# CDTV-SCSI-SD.net
KiCad netlist of a schematic drawn in EAGLE
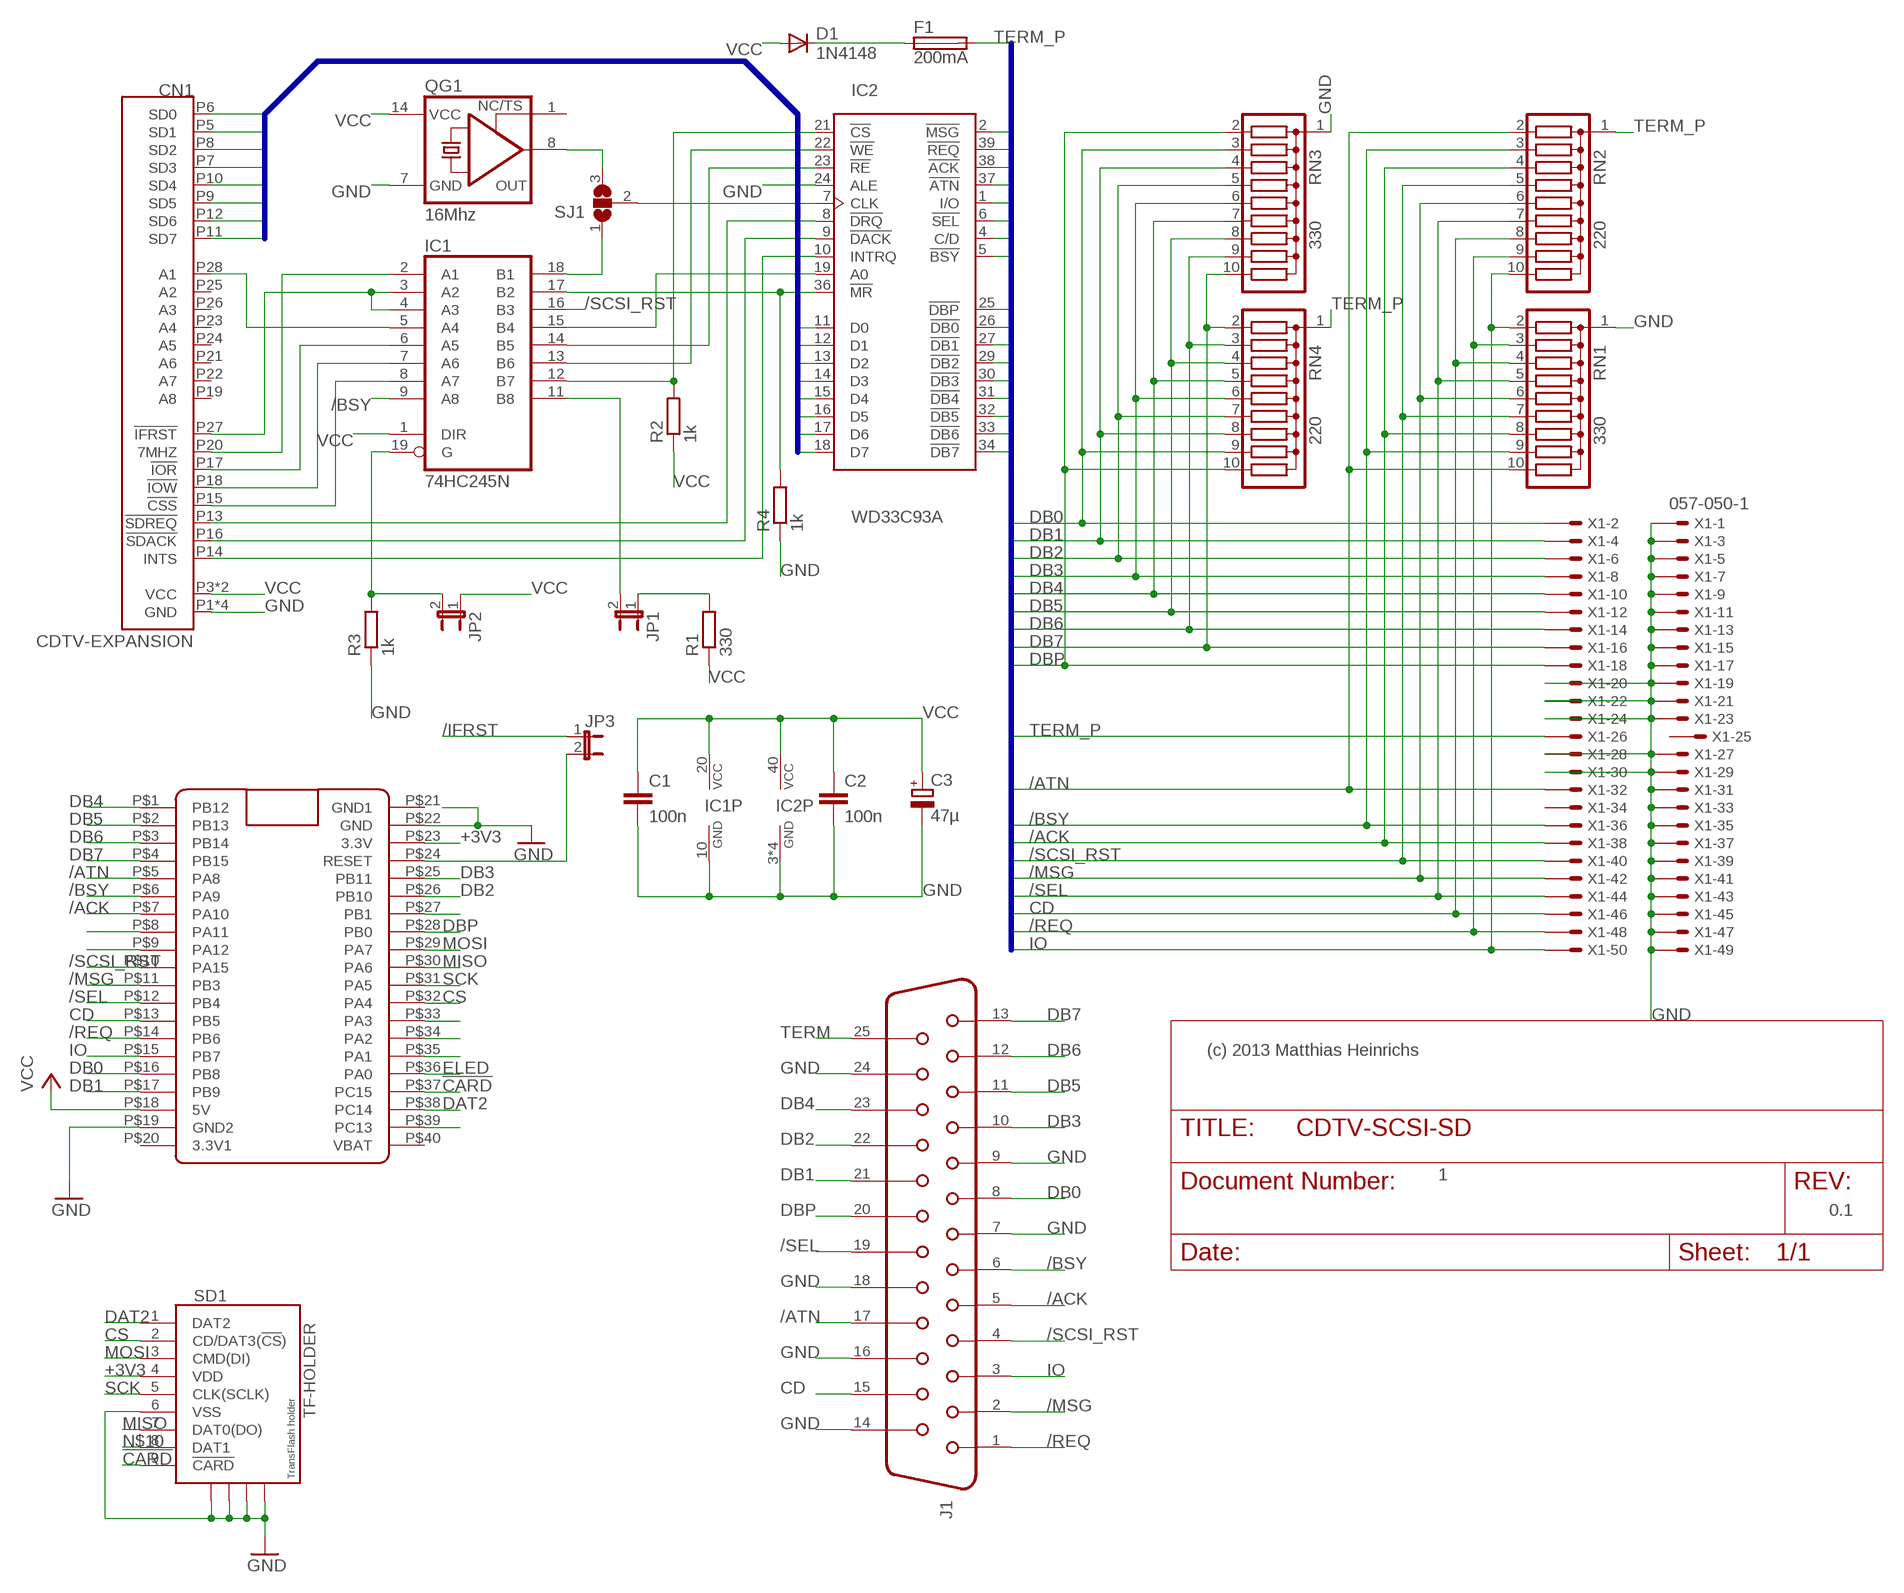
[diagram p0: schematic, sheet 1]

(export (version "E")
  (design (tool "Eeschema 10.0.6"))
  (components
    (comp (ref "C1")
      (value "100n")
      (footprint "eagle-import:C025-024X044")
      (libsource (lib "eagle-import") (part "C-EU025-024X044"))
    )
    (comp (ref "C2")
      (value "100n")
      (footprint "eagle-import:C025-024X044")
      (libsource (lib "eagle-import") (part "C-EU025-024X044"))
    )
    (comp (ref "C3")
      (value "47µ")
      (footprint "eagle-import:E2,5-6E")
      (libsource (lib "eagle-import") (part "CPOL-EUE2,5-6E"))
    )
    (comp (ref "CN1")
      (value "CDTV-EXPANSION")
      (footprint "eagle-import:CDTV-SLOT")
      (libsource (lib "eagle-import") (part "CDTV-EXPANSION"))
    )
    (comp (ref "D1")
      (value "1N4148")
      (footprint "eagle-import:DO35-7")
      (libsource (lib "eagle-import") (part "1N4148DO35-7"))
    )
    (comp (ref "F1")
      (value "200mA")
      (footprint "eagle-import:TE5")
      (libsource (lib "eagle-import") (part "FUSETE5"))
    )
    (comp (ref "IC1")
      (value "74HC245N")
      (footprint "eagle-import:DIL20")
      (libsource (lib "eagle-import") (part "74245NHC"))
    )
    (comp (ref "IC2")
      (value "WD33C93A")
      (footprint "eagle-import:DIP40-6")
      (libsource (lib "eagle-import") (part "WD33C93"))
    )
    (comp (ref "J1")
      (value "61802529321")
      (footprint "eagle-import:61802529321")
      (libsource (lib "eagle-import") (part "61802529321"))
    )
    (comp (ref "JP1")
      (value "JP1E")
      (footprint "eagle-import:JP1")
      (libsource (lib "eagle-import") (part "JP1E"))
    )
    (comp (ref "JP2")
      (value "JP1E")
      (footprint "eagle-import:JP1")
      (libsource (lib "eagle-import") (part "JP1E"))
    )
    (comp (ref "JP3")
      (value "JP1E")
      (footprint "eagle-import:JP1")
      (libsource (lib "eagle-import") (part "JP1E"))
    )
    (comp (ref "QG1")
      (value "16Mhz")
      (footprint "eagle-import:DIL14S")
      (libsource (lib "eagle-import") (part "XO-14"))
    )
    (comp (ref "R1")
      (value "330")
      (footprint "eagle-import:0207_7")
      (libsource (lib "eagle-import") (part "R-EU_0207/7"))
    )
    (comp (ref "R2")
      (value "1k")
      (footprint "eagle-import:0207_7")
      (libsource (lib "eagle-import") (part "R-EU_0207/7"))
    )
    (comp (ref "R3")
      (value "1k")
      (footprint "eagle-import:0207_7")
      (libsource (lib "eagle-import") (part "R-EU_0207/7"))
    )
    (comp (ref "R4")
      (value "1k")
      (footprint "eagle-import:0207_7")
      (libsource (lib "eagle-import") (part "R-EU_0207/7"))
    )
    (comp (ref "RN1")
      (value "330")
      (footprint "eagle-import:SIL10")
      (libsource (lib "eagle-import") (part "G09R"))
    )
    (comp (ref "RN2")
      (value "220")
      (footprint "eagle-import:SIL10")
      (libsource (lib "eagle-import") (part "G09R"))
    )
    (comp (ref "RN3")
      (value "330")
      (footprint "eagle-import:SIL10")
      (libsource (lib "eagle-import") (part "G09R"))
    )
    (comp (ref "RN4")
      (value "220")
      (footprint "eagle-import:SIL10")
      (libsource (lib "eagle-import") (part "G09R"))
    )
    (comp (ref "SD1")
      (value "TF-HOLDER")
      (footprint "eagle-import:TF-PULL")
      (libsource (lib "eagle-import") (part "TF-HOLDER"))
    )
    (comp (ref "SJ1")
      (value "SJ2W")
      (footprint "eagle-import:SJ_2")
      (libsource (lib "eagle-import") (part "SJ2W"))
    )
    (comp (ref "U$1")
      (value "BLUE_PILL")
      (footprint "eagle-import:BLUE_PILL")
      (libsource (lib "eagle-import") (part "BLUE_PILL"))
    )
    (comp (ref "X1")
      (value "057-050-1")
      (footprint "eagle-import:057-050-1")
      (libsource (lib "eagle-import") (part "057-050-1"))
    )
  )
  (nets
    (net (code "1") (name "/+3V3") (class "Default")
      (node (ref "SD1") (pin "4") (pinfunction "VDD_4") (pintype "power_in"))
      (node (ref "U$1") (pin "P$23") (pinfunction "3.3V_P$23") (pintype "bidirectional"))
    )
    (net (code "2") (name "/CD") (class "Default")
      (node (ref "IC2") (pin "4") (pinfunction "C/D_4") (pintype "bidirectional"))
      (node (ref "J1") (pin "15") (pinfunction "15_15") (pintype "bidirectional"))
      (node (ref "RN1") (pin "4") (pinfunction "4_4") (pintype "passive"))
      (node (ref "RN2") (pin "8") (pinfunction "8_8") (pintype "passive"))
      (node (ref "U$1") (pin "P$13") (pinfunction "PB5_P$13") (pintype "bidirectional"))
      (node (ref "X1") (pin "46") (pinfunction "S_46") (pintype "passive"))
    )
    (net (code "3") (name "/CS") (class "Default")
      (node (ref "SD1") (pin "2") (pinfunction "CD/DAT3(~{CS})_2") (pintype "bidirectional"))
      (node (ref "U$1") (pin "P$32") (pinfunction "PA4_P$32") (pintype "bidirectional"))
    )
    (net (code "4") (name "/DAT2") (class "Default")
      (node (ref "SD1") (pin "1") (pinfunction "DAT2_1") (pintype "bidirectional"))
      (node (ref "U$1") (pin "P$38") (pinfunction "PC14_P$38") (pintype "bidirectional"))
    )
    (net (code "5") (name "/DB0") (class "Default")
      (node (ref "IC2") (pin "26") (pinfunction "~{DB0}_26") (pintype "bidirectional"))
      (node (ref "J1") (pin "8") (pinfunction "8_8") (pintype "bidirectional"))
      (node (ref "RN3") (pin "3") (pinfunction "3_3") (pintype "passive"))
      (node (ref "RN4") (pin "9") (pinfunction "9_9") (pintype "passive"))
      (node (ref "U$1") (pin "P$16") (pinfunction "PB8_P$16") (pintype "bidirectional"))
      (node (ref "X1") (pin "2") (pinfunction "S_2") (pintype "passive"))
    )
    (net (code "6") (name "/DB1") (class "Default")
      (node (ref "IC2") (pin "27") (pinfunction "~{DB1}_27") (pintype "bidirectional"))
      (node (ref "J1") (pin "21") (pinfunction "21_21") (pintype "bidirectional"))
      (node (ref "RN3") (pin "4") (pinfunction "4_4") (pintype "passive"))
      (node (ref "RN4") (pin "8") (pinfunction "8_8") (pintype "passive"))
      (node (ref "U$1") (pin "P$17") (pinfunction "PB9_P$17") (pintype "bidirectional"))
      (node (ref "X1") (pin "4") (pinfunction "S_4") (pintype "passive"))
    )
    (net (code "7") (name "/DB2") (class "Default")
      (node (ref "IC2") (pin "29") (pinfunction "~{DB2}_29") (pintype "bidirectional"))
      (node (ref "J1") (pin "22") (pinfunction "22_22") (pintype "bidirectional"))
      (node (ref "RN3") (pin "5") (pinfunction "5_5") (pintype "passive"))
      (node (ref "RN4") (pin "7") (pinfunction "7_7") (pintype "passive"))
      (node (ref "U$1") (pin "P$26") (pinfunction "PB10_P$26") (pintype "bidirectional"))
      (node (ref "X1") (pin "6") (pinfunction "S_6") (pintype "passive"))
    )
    (net (code "8") (name "/DB3") (class "Default")
      (node (ref "IC2") (pin "30") (pinfunction "~{DB3}_30") (pintype "bidirectional"))
      (node (ref "J1") (pin "10") (pinfunction "10_10") (pintype "bidirectional"))
      (node (ref "RN3") (pin "6") (pinfunction "6_6") (pintype "passive"))
      (node (ref "RN4") (pin "6") (pinfunction "6_6") (pintype "passive"))
      (node (ref "U$1") (pin "P$25") (pinfunction "PB11_P$25") (pintype "bidirectional"))
      (node (ref "X1") (pin "8") (pinfunction "S_8") (pintype "passive"))
    )
    (net (code "9") (name "/DB4") (class "Default")
      (node (ref "IC2") (pin "31") (pinfunction "~{DB4}_31") (pintype "bidirectional"))
      (node (ref "J1") (pin "23") (pinfunction "23_23") (pintype "bidirectional"))
      (node (ref "RN3") (pin "7") (pinfunction "7_7") (pintype "passive"))
      (node (ref "RN4") (pin "5") (pinfunction "5_5") (pintype "passive"))
      (node (ref "U$1") (pin "P$1") (pinfunction "PB12_P$1") (pintype "bidirectional"))
      (node (ref "X1") (pin "10") (pinfunction "S_10") (pintype "passive"))
    )
    (net (code "10") (name "/DB5") (class "Default")
      (node (ref "IC2") (pin "32") (pinfunction "~{DB5}_32") (pintype "bidirectional"))
      (node (ref "J1") (pin "11") (pinfunction "11_11") (pintype "bidirectional"))
      (node (ref "RN3") (pin "8") (pinfunction "8_8") (pintype "passive"))
      (node (ref "RN4") (pin "4") (pinfunction "4_4") (pintype "passive"))
      (node (ref "U$1") (pin "P$2") (pinfunction "PB13_P$2") (pintype "bidirectional"))
      (node (ref "X1") (pin "12") (pinfunction "S_12") (pintype "passive"))
    )
    (net (code "11") (name "/DB6") (class "Default")
      (node (ref "IC2") (pin "33") (pinfunction "~{DB6}_33") (pintype "bidirectional"))
      (node (ref "J1") (pin "12") (pinfunction "12_12") (pintype "bidirectional"))
      (node (ref "RN3") (pin "9") (pinfunction "9_9") (pintype "passive"))
      (node (ref "RN4") (pin "3") (pinfunction "3_3") (pintype "passive"))
      (node (ref "U$1") (pin "P$3") (pinfunction "PB14_P$3") (pintype "bidirectional"))
      (node (ref "X1") (pin "14") (pinfunction "S_14") (pintype "passive"))
    )
    (net (code "12") (name "/DB7") (class "Default")
      (node (ref "IC2") (pin "34") (pinfunction "~{DB7}_34") (pintype "bidirectional"))
      (node (ref "J1") (pin "13") (pinfunction "13_13") (pintype "bidirectional"))
      (node (ref "RN3") (pin "10") (pinfunction "10_10") (pintype "passive"))
      (node (ref "RN4") (pin "2") (pinfunction "2_2") (pintype "passive"))
      (node (ref "U$1") (pin "P$4") (pinfunction "PB15_P$4") (pintype "bidirectional"))
      (node (ref "X1") (pin "16") (pinfunction "S_16") (pintype "passive"))
    )
    (net (code "13") (name "/DBP") (class "Default")
      (node (ref "IC2") (pin "25") (pinfunction "~{DBP}_25") (pintype "bidirectional"))
      (node (ref "J1") (pin "20") (pinfunction "20_20") (pintype "bidirectional"))
      (node (ref "RN3") (pin "2") (pinfunction "2_2") (pintype "passive"))
      (node (ref "RN4") (pin "10") (pinfunction "10_10") (pintype "passive"))
      (node (ref "U$1") (pin "P$28") (pinfunction "PB0_P$28") (pintype "bidirectional"))
      (node (ref "X1") (pin "18") (pinfunction "S_18") (pintype "passive"))
    )
    (net (code "14") (name "/ELED") (class "Default")
      (node (ref "U$1") (pin "P$36") (pinfunction "PA0_P$36") (pintype "bidirectional"))
    )
    (net (code "15") (name "/GND1") (class "Default")
      (node (ref "U$1") (pin "P$21") (pinfunction "GND1_P$21") (pintype "power_in"))
    )
    (net (code "16") (name "/IO") (class "Default")
      (node (ref "IC2") (pin "1") (pinfunction "I/O_1") (pintype "bidirectional"))
      (node (ref "J1") (pin "3") (pinfunction "3_3") (pintype "bidirectional"))
      (node (ref "RN1") (pin "2") (pinfunction "2_2") (pintype "passive"))
      (node (ref "RN2") (pin "10") (pinfunction "10_10") (pintype "passive"))
      (node (ref "U$1") (pin "P$15") (pinfunction "PB7_P$15") (pintype "bidirectional"))
      (node (ref "X1") (pin "50") (pinfunction "S_50") (pintype "passive"))
    )
    (net (code "17") (name "/MISO") (class "Default")
      (node (ref "SD1") (pin "7") (pinfunction "DAT0(DO)_7") (pintype "bidirectional"))
      (node (ref "U$1") (pin "P$30") (pinfunction "PA6_P$30") (pintype "bidirectional"))
    )
    (net (code "18") (name "/MOSI") (class "Default")
      (node (ref "SD1") (pin "3") (pinfunction "CMD(DI)_3") (pintype "bidirectional"))
      (node (ref "U$1") (pin "P$29") (pinfunction "PA7_P$29") (pintype "bidirectional"))
    )
    (net (code "19") (name "/N$10") (class "Default")
      (node (ref "SD1") (pin "8") (pinfunction "DAT1_8") (pintype "bidirectional"))
    )
    (net (code "20") (name "/SCK") (class "Default")
      (node (ref "SD1") (pin "5") (pinfunction "CLK(SCLK)_5") (pintype "input"))
      (node (ref "U$1") (pin "P$31") (pinfunction "PA5_P$31") (pintype "bidirectional"))
    )
    (net (code "21") (name "/SD0") (class "Default")
      (node (ref "CN1") (pin "P6") (pinfunction "SD0_P6") (pintype "bidirectional"))
      (node (ref "IC2") (pin "11") (pinfunction "D0_11") (pintype "bidirectional"))
    )
    (net (code "22") (name "/SD1") (class "Default")
      (node (ref "CN1") (pin "P5") (pinfunction "SD1_P5") (pintype "bidirectional"))
      (node (ref "IC2") (pin "12") (pinfunction "D1_12") (pintype "bidirectional"))
    )
    (net (code "23") (name "/SD2") (class "Default")
      (node (ref "CN1") (pin "P8") (pinfunction "SD2_P8") (pintype "bidirectional"))
      (node (ref "IC2") (pin "13") (pinfunction "D2_13") (pintype "bidirectional"))
    )
    (net (code "24") (name "/SD3") (class "Default")
      (node (ref "CN1") (pin "P7") (pinfunction "SD3_P7") (pintype "bidirectional"))
      (node (ref "IC2") (pin "14") (pinfunction "D3_14") (pintype "bidirectional"))
    )
    (net (code "25") (name "/SD4") (class "Default")
      (node (ref "CN1") (pin "P10") (pinfunction "SD4_P10") (pintype "bidirectional"))
      (node (ref "IC2") (pin "15") (pinfunction "D4_15") (pintype "bidirectional"))
    )
    (net (code "26") (name "/SD5") (class "Default")
      (node (ref "CN1") (pin "P9") (pinfunction "SD5_P9") (pintype "bidirectional"))
      (node (ref "IC2") (pin "16") (pinfunction "D5_16") (pintype "bidirectional"))
    )
    (net (code "27") (name "/SD6") (class "Default")
      (node (ref "CN1") (pin "P12") (pinfunction "SD6_P12") (pintype "bidirectional"))
      (node (ref "IC2") (pin "17") (pinfunction "D6_17") (pintype "bidirectional"))
    )
    (net (code "28") (name "/SD7") (class "Default")
      (node (ref "CN1") (pin "P11") (pinfunction "SD7_P11") (pintype "bidirectional"))
      (node (ref "IC2") (pin "18") (pinfunction "D7_18") (pintype "bidirectional"))
    )
    (net (code "29") (name "/TERM") (class "Default")
      (node (ref "J1") (pin "25") (pinfunction "25_25") (pintype "bidirectional"))
    )
    (net (code "30") (name "/TERM_P") (class "Default")
      (node (ref "F1") (pin "2") (pinfunction "2_2") (pintype "passive"))
      (node (ref "RN2") (pin "1") (pinfunction "1_1") (pintype "passive"))
      (node (ref "RN4") (pin "1") (pinfunction "1_1") (pintype "passive"))
      (node (ref "X1") (pin "26") (pinfunction "S_26") (pintype "passive"))
    )
    (net (code "31") (name "/{slash}ACK") (class "Default")
      (node (ref "IC2") (pin "38") (pinfunction "~{ACK}_38") (pintype "bidirectional"))
      (node (ref "J1") (pin "5") (pinfunction "5_5") (pintype "bidirectional"))
      (node (ref "RN1") (pin "8") (pinfunction "8_8") (pintype "passive"))
      (node (ref "RN2") (pin "4") (pinfunction "4_4") (pintype "passive"))
      (node (ref "U$1") (pin "P$7") (pinfunction "PA10_P$7") (pintype "bidirectional"))
      (node (ref "X1") (pin "38") (pinfunction "S_38") (pintype "passive"))
    )
    (net (code "32") (name "/{slash}ATN") (class "Default")
      (node (ref "IC2") (pin "37") (pinfunction "~{ATN}_37") (pintype "bidirectional"))
      (node (ref "J1") (pin "17") (pinfunction "17_17") (pintype "bidirectional"))
      (node (ref "RN1") (pin "10") (pinfunction "10_10") (pintype "passive"))
      (node (ref "RN2") (pin "2") (pinfunction "2_2") (pintype "passive"))
      (node (ref "U$1") (pin "P$5") (pinfunction "PA8_P$5") (pintype "bidirectional"))
      (node (ref "X1") (pin "32") (pinfunction "S_32") (pintype "passive"))
    )
    (net (code "33") (name "/{slash}BSY") (class "Default")
      (node (ref "IC1") (pin "9") (pinfunction "A8_9") (pintype "bidirectional"))
      (node (ref "IC2") (pin "5") (pinfunction "~{BSY}_5") (pintype "bidirectional"))
      (node (ref "J1") (pin "6") (pinfunction "6_6") (pintype "bidirectional"))
      (node (ref "RN1") (pin "9") (pinfunction "9_9") (pintype "passive"))
      (node (ref "RN2") (pin "3") (pinfunction "3_3") (pintype "passive"))
      (node (ref "U$1") (pin "P$6") (pinfunction "PA9_P$6") (pintype "bidirectional"))
      (node (ref "X1") (pin "36") (pinfunction "S_36") (pintype "passive"))
    )
    (net (code "34") (name "/{slash}IFRST") (class "Default")
      (node (ref "CN1") (pin "P27") (pinfunction "~{IFRST}_P27") (pintype "output"))
      (node (ref "IC1") (pin "3") (pinfunction "A2_3") (pintype "bidirectional"))
      (node (ref "IC1") (pin "4") (pinfunction "A3_4") (pintype "bidirectional"))
      (node (ref "JP3") (pin "1") (pinfunction "1_1") (pintype "passive"))
    )
    (net (code "35") (name "/{slash}MSG") (class "Default")
      (node (ref "IC2") (pin "2") (pinfunction "~{MSG}_2") (pintype "bidirectional"))
      (node (ref "J1") (pin "2") (pinfunction "2_2") (pintype "bidirectional"))
      (node (ref "RN1") (pin "6") (pinfunction "6_6") (pintype "passive"))
      (node (ref "RN2") (pin "6") (pinfunction "6_6") (pintype "passive"))
      (node (ref "U$1") (pin "P$11") (pinfunction "PB3_P$11") (pintype "bidirectional"))
      (node (ref "X1") (pin "42") (pinfunction "S_42") (pintype "passive"))
    )
    (net (code "36") (name "/{slash}REQ") (class "Default")
      (node (ref "IC2") (pin "39") (pinfunction "~{REQ}_39") (pintype "bidirectional"))
      (node (ref "J1") (pin "1") (pinfunction "1_1") (pintype "bidirectional"))
      (node (ref "RN1") (pin "3") (pinfunction "3_3") (pintype "passive"))
      (node (ref "RN2") (pin "9") (pinfunction "9_9") (pintype "passive"))
      (node (ref "U$1") (pin "P$14") (pinfunction "PB6_P$14") (pintype "bidirectional"))
      (node (ref "X1") (pin "48") (pinfunction "S_48") (pintype "passive"))
    )
    (net (code "37") (name "/{slash}SCSI_RST") (class "Default")
      (node (ref "IC1") (pin "16") (pinfunction "B3_16") (pintype "bidirectional"))
      (node (ref "J1") (pin "4") (pinfunction "4_4") (pintype "bidirectional"))
      (node (ref "RN1") (pin "7") (pinfunction "7_7") (pintype "passive"))
      (node (ref "RN2") (pin "5") (pinfunction "5_5") (pintype "passive"))
      (node (ref "U$1") (pin "P$10") (pinfunction "PA15_P$10") (pintype "bidirectional"))
      (node (ref "X1") (pin "40") (pinfunction "S_40") (pintype "passive"))
    )
    (net (code "38") (name "/{slash}SEL") (class "Default")
      (node (ref "IC2") (pin "6") (pinfunction "~{SEL}_6") (pintype "bidirectional"))
      (node (ref "J1") (pin "19") (pinfunction "19_19") (pintype "bidirectional"))
      (node (ref "RN1") (pin "5") (pinfunction "5_5") (pintype "passive"))
      (node (ref "RN2") (pin "7") (pinfunction "7_7") (pintype "passive"))
      (node (ref "U$1") (pin "P$12") (pinfunction "PB4_P$12") (pintype "bidirectional"))
      (node (ref "X1") (pin "44") (pinfunction "S_44") (pintype "passive"))
    )
    (net (code "39") (name "/~{CARD}") (class "Default")
      (node (ref "SD1") (pin "9") (pinfunction "~{CARD}_9") (pintype "passive"))
      (node (ref "U$1") (pin "P$37") (pinfunction "PC15_P$37") (pintype "bidirectional"))
    )
    (net (code "40") (name "GND") (class "Default")
      (node (ref "C1") (pin "2") (pinfunction "2_2") (pintype "passive"))
      (node (ref "C2") (pin "2") (pinfunction "2_2") (pintype "passive"))
      (node (ref "C3") (pin "-") (pinfunction "-_-") (pintype "passive"))
      (node (ref "CN1") (pin "P1") (pinfunction "GND_P1") (pintype "power_in"))
      (node (ref "CN1") (pin "P2") (pinfunction "GND_P2") (pintype "power_in"))
      (node (ref "CN1") (pin "P29") (pinfunction "GND_P29") (pintype "power_in"))
      (node (ref "CN1") (pin "P30") (pinfunction "GND_P30") (pintype "power_in"))
      (node (ref "IC1") (pin "10") (pinfunction "GND_10") (pintype "power_in"))
      (node (ref "IC2") (pin "20") (pinfunction "GND1_20") (pintype "power_in"))
      (node (ref "IC2") (pin "24") (pinfunction "ALE_24") (pintype "bidirectional"))
      (node (ref "IC2") (pin "28") (pinfunction "GND1_28") (pintype "power_in"))
      (node (ref "IC2") (pin "3") (pinfunction "GND1_3") (pintype "power_in"))
      (node (ref "IC2") (pin "35") (pinfunction "GND1_35") (pintype "power_in"))
      (node (ref "J1") (pin "14") (pinfunction "14_14") (pintype "bidirectional"))
      (node (ref "J1") (pin "16") (pinfunction "16_16") (pintype "bidirectional"))
      (node (ref "J1") (pin "18") (pinfunction "18_18") (pintype "bidirectional"))
      (node (ref "J1") (pin "24") (pinfunction "24_24") (pintype "bidirectional"))
      (node (ref "J1") (pin "7") (pinfunction "7_7") (pintype "bidirectional"))
      (node (ref "J1") (pin "9") (pinfunction "9_9") (pintype "bidirectional"))
      (node (ref "QG1") (pin "7") (pinfunction "GND_7") (pintype "power_in"))
      (node (ref "R3") (pin "1") (pinfunction "1_1") (pintype "passive"))
      (node (ref "R4") (pin "1") (pinfunction "1_1") (pintype "passive"))
      (node (ref "RN1") (pin "1") (pinfunction "1_1") (pintype "passive"))
      (node (ref "RN3") (pin "1") (pinfunction "1_1") (pintype "passive"))
      (node (ref "SD1") (pin "6") (pinfunction "VSS_6") (pintype "power_in"))
      (node (ref "SD1") (pin "S1") (pinfunction "S1_S1") (pintype "passive"))
      (node (ref "SD1") (pin "S2") (pinfunction "S2_S2") (pintype "passive"))
      (node (ref "SD1") (pin "S3") (pinfunction "S3_S3") (pintype "passive"))
      (node (ref "SD1") (pin "S4") (pinfunction "S4_S4") (pintype "passive"))
      (node (ref "U$1") (pin "P$19") (pinfunction "GND2_P$19") (pintype "bidirectional"))
      (node (ref "U$1") (pin "P$22") (pinfunction "GND_P$22") (pintype "bidirectional"))
      (node (ref "X1") (pin "1") (pinfunction "S_1") (pintype "passive"))
      (node (ref "X1") (pin "11") (pinfunction "S_11") (pintype "passive"))
      (node (ref "X1") (pin "13") (pinfunction "S_13") (pintype "passive"))
      (node (ref "X1") (pin "15") (pinfunction "S_15") (pintype "passive"))
      (node (ref "X1") (pin "17") (pinfunction "S_17") (pintype "passive"))
      (node (ref "X1") (pin "19") (pinfunction "S_19") (pintype "passive"))
      (node (ref "X1") (pin "20") (pinfunction "S_20") (pintype "passive"))
      (node (ref "X1") (pin "21") (pinfunction "S_21") (pintype "passive"))
      (node (ref "X1") (pin "22") (pinfunction "S_22") (pintype "passive"))
      (node (ref "X1") (pin "23") (pinfunction "S_23") (pintype "passive"))
      (node (ref "X1") (pin "24") (pinfunction "S_24") (pintype "passive"))
      (node (ref "X1") (pin "27") (pinfunction "S_27") (pintype "passive"))
      (node (ref "X1") (pin "28") (pinfunction "S_28") (pintype "passive"))
      (node (ref "X1") (pin "29") (pinfunction "S_29") (pintype "passive"))
      (node (ref "X1") (pin "3") (pinfunction "S_3") (pintype "passive"))
      (node (ref "X1") (pin "30") (pinfunction "S_30") (pintype "passive"))
      (node (ref "X1") (pin "31") (pinfunction "S_31") (pintype "passive"))
      (node (ref "X1") (pin "33") (pinfunction "S_33") (pintype "passive"))
      (node (ref "X1") (pin "35") (pinfunction "S_35") (pintype "passive"))
      (node (ref "X1") (pin "37") (pinfunction "S_37") (pintype "passive"))
      (node (ref "X1") (pin "39") (pinfunction "S_39") (pintype "passive"))
      (node (ref "X1") (pin "41") (pinfunction "S_41") (pintype "passive"))
      (node (ref "X1") (pin "43") (pinfunction "S_43") (pintype "passive"))
      (node (ref "X1") (pin "45") (pinfunction "S_45") (pintype "passive"))
      (node (ref "X1") (pin "47") (pinfunction "S_47") (pintype "passive"))
      (node (ref "X1") (pin "49") (pinfunction "S_49") (pintype "passive"))
      (node (ref "X1") (pin "5") (pinfunction "S_5") (pintype "passive"))
      (node (ref "X1") (pin "7") (pinfunction "S_7") (pintype "passive"))
      (node (ref "X1") (pin "9") (pinfunction "S_9") (pintype "passive"))
    )
    (net (code "41") (name "Net-(CN1-7MHZ)") (class "Default")
      (node (ref "CN1") (pin "P20") (pinfunction "7MHZ_P20") (pintype "output"))
      (node (ref "IC1") (pin "2") (pinfunction "A1_2") (pintype "bidirectional"))
    )
    (net (code "42") (name "Net-(CN1-A1)") (class "Default")
      (node (ref "CN1") (pin "P28") (pinfunction "A1_P28") (pintype "output"))
      (node (ref "IC1") (pin "5") (pinfunction "A4_5") (pintype "bidirectional"))
    )
    (net (code "43") (name "Net-(CN1-INTS)") (class "Default")
      (node (ref "CN1") (pin "P14") (pinfunction "INTS_P14") (pintype "input"))
      (node (ref "IC2") (pin "10") (pinfunction "INTRQ_10") (pintype "bidirectional"))
    )
    (net (code "44") (name "Net-(CN1-~{CSS})") (class "Default")
      (node (ref "CN1") (pin "P15") (pinfunction "~{CSS}_P15") (pintype "output"))
      (node (ref "IC1") (pin "8") (pinfunction "A7_8") (pintype "bidirectional"))
    )
    (net (code "45") (name "Net-(CN1-~{IOR})") (class "Default")
      (node (ref "CN1") (pin "P17") (pinfunction "~{IOR}_P17") (pintype "output"))
      (node (ref "IC1") (pin "6") (pinfunction "A5_6") (pintype "bidirectional"))
    )
    (net (code "46") (name "Net-(CN1-~{IOW})") (class "Default")
      (node (ref "CN1") (pin "P18") (pinfunction "~{IOW}_P18") (pintype "output"))
      (node (ref "IC1") (pin "7") (pinfunction "A6_7") (pintype "bidirectional"))
    )
    (net (code "47") (name "Net-(CN1-~{SDACK})") (class "Default")
      (node (ref "CN1") (pin "P16") (pinfunction "~{SDACK}_P16") (pintype "output"))
      (node (ref "IC2") (pin "9") (pinfunction "~{DACK}_9") (pintype "bidirectional"))
    )
    (net (code "48") (name "Net-(CN1-~{SDREQ})") (class "Default")
      (node (ref "CN1") (pin "P13") (pinfunction "~{SDREQ}_P13") (pintype "output"))
      (node (ref "IC2") (pin "8") (pinfunction "~{DRQ}_8") (pintype "bidirectional"))
    )
    (net (code "49") (name "Net-(D1-PadC)") (class "Default")
      (node (ref "D1") (pin "C") (pinfunction "C_C") (pintype "passive"))
      (node (ref "F1") (pin "1") (pinfunction "1_1") (pintype "passive"))
    )
    (net (code "50") (name "Net-(IC1A-B1)") (class "Default")
      (node (ref "IC1") (pin "18") (pinfunction "B1_18") (pintype "bidirectional"))
      (node (ref "SJ1") (pin "1") (pinfunction "1_1") (pintype "passive"))
    )
    (net (code "51") (name "Net-(IC1A-B2)") (class "Default")
      (node (ref "IC1") (pin "17") (pinfunction "B2_17") (pintype "bidirectional"))
      (node (ref "IC2") (pin "36") (pinfunction "~{MR}_36") (pintype "bidirectional"))
      (node (ref "R4") (pin "2") (pinfunction "2_2") (pintype "passive"))
    )
    (net (code "52") (name "Net-(IC1A-B4)") (class "Default")
      (node (ref "IC1") (pin "15") (pinfunction "B4_15") (pintype "bidirectional"))
      (node (ref "IC2") (pin "19") (pinfunction "A0_19") (pintype "bidirectional"))
    )
    (net (code "53") (name "Net-(IC1A-B5)") (class "Default")
      (node (ref "IC1") (pin "14") (pinfunction "B5_14") (pintype "bidirectional"))
      (node (ref "IC2") (pin "23") (pinfunction "~{RE}_23") (pintype "bidirectional"))
    )
    (net (code "54") (name "Net-(IC1A-B6)") (class "Default")
      (node (ref "IC1") (pin "13") (pinfunction "B6_13") (pintype "bidirectional"))
      (node (ref "IC2") (pin "22") (pinfunction "~{WE}_22") (pintype "bidirectional"))
    )
    (net (code "55") (name "Net-(IC1A-B7)") (class "Default")
      (node (ref "IC1") (pin "12") (pinfunction "B7_12") (pintype "bidirectional"))
      (node (ref "IC2") (pin "21") (pinfunction "~{CS}_21") (pintype "bidirectional"))
      (node (ref "R2") (pin "2") (pinfunction "2_2") (pintype "passive"))
    )
    (net (code "56") (name "Net-(IC1A-B8)") (class "Default")
      (node (ref "IC1") (pin "11") (pinfunction "B8_11") (pintype "bidirectional"))
      (node (ref "JP1") (pin "2") (pinfunction "2_2") (pintype "passive"))
    )
    (net (code "57") (name "Net-(IC1A-G)") (class "Default")
      (node (ref "IC1") (pin "19") (pinfunction "G_19") (pintype "input"))
      (node (ref "JP2") (pin "2") (pinfunction "2_2") (pintype "passive"))
      (node (ref "R3") (pin "2") (pinfunction "2_2") (pintype "passive"))
    )
    (net (code "58") (name "Net-(IC2A-CLK)") (class "Default")
      (node (ref "IC2") (pin "7") (pinfunction "CLK_7") (pintype "input"))
      (node (ref "SJ1") (pin "2") (pinfunction "2_2") (pintype "passive"))
    )
    (net (code "59") (name "Net-(JP1-Pad1)") (class "Default")
      (node (ref "JP1") (pin "1") (pinfunction "1_1") (pintype "passive"))
      (node (ref "R1") (pin "2") (pinfunction "2_2") (pintype "passive"))
    )
    (net (code "60") (name "Net-(QG1-OUT)") (class "Default")
      (node (ref "QG1") (pin "8") (pinfunction "OUT_8") (pintype "output"))
      (node (ref "SJ1") (pin "3") (pinfunction "3_3") (pintype "passive"))
    )
    (net (code "61") (name "Net-(U$1-RESET)") (class "Default")
      (node (ref "JP3") (pin "2") (pinfunction "2_2") (pintype "passive"))
      (node (ref "U$1") (pin "P$24") (pinfunction "RESET_P$24") (pintype "bidirectional"))
    )
    (net (code "62") (name "VCC") (class "Default")
      (node (ref "C1") (pin "1") (pinfunction "1_1") (pintype "passive"))
      (node (ref "C2") (pin "1") (pinfunction "1_1") (pintype "passive"))
      (node (ref "C3") (pin "+") (pinfunction "+_+") (pintype "passive"))
      (node (ref "CN1") (pin "P3") (pinfunction "VCC_P3") (pintype "power_in"))
      (node (ref "CN1") (pin "P4") (pinfunction "VCC_P4") (pintype "power_in"))
      (node (ref "D1") (pin "A") (pinfunction "A_A") (pintype "passive"))
      (node (ref "IC1") (pin "1") (pinfunction "DIR_1") (pintype "input"))
      (node (ref "IC1") (pin "20") (pinfunction "VCC_20") (pintype "power_in"))
      (node (ref "IC2") (pin "40") (pinfunction "VCC1_40") (pintype "power_in"))
      (node (ref "JP2") (pin "1") (pinfunction "1_1") (pintype "passive"))
      (node (ref "QG1") (pin "14") (pinfunction "VCC_14") (pintype "power_in"))
      (node (ref "R1") (pin "1") (pinfunction "1_1") (pintype "passive"))
      (node (ref "R2") (pin "1") (pinfunction "1_1") (pintype "passive"))
      (node (ref "U$1") (pin "P$18") (pinfunction "5V_P$18") (pintype "bidirectional"))
    )
    (net (code "63") (name "unconnected-(CN1-A2-PadP25)") (class "Default")
      (node (ref "CN1") (pin "P25") (pinfunction "A2_P25") (pintype "output"))
    )
    (net (code "64") (name "unconnected-(CN1-A3-PadP26)") (class "Default")
      (node (ref "CN1") (pin "P26") (pinfunction "A3_P26") (pintype "output"))
    )
    (net (code "65") (name "unconnected-(CN1-A4-PadP23)") (class "Default")
      (node (ref "CN1") (pin "P23") (pinfunction "A4_P23") (pintype "output"))
    )
    (net (code "66") (name "unconnected-(CN1-A5-PadP24)") (class "Default")
      (node (ref "CN1") (pin "P24") (pinfunction "A5_P24") (pintype "output"))
    )
    (net (code "67") (name "unconnected-(CN1-A6-PadP21)") (class "Default")
      (node (ref "CN1") (pin "P21") (pinfunction "A6_P21") (pintype "output"))
    )
    (net (code "68") (name "unconnected-(CN1-A7-PadP22)") (class "Default")
      (node (ref "CN1") (pin "P22") (pinfunction "A7_P22") (pintype "output"))
    )
    (net (code "69") (name "unconnected-(CN1-A8-PadP19)") (class "Default")
      (node (ref "CN1") (pin "P19") (pinfunction "A8_P19") (pintype "output"))
    )
    (net (code "70") (name "unconnected-(QG1-TS-Pad1)") (class "Default")
      (node (ref "QG1") (pin "1") (pinfunction "TS_1") (pintype "passive"))
    )
    (net (code "71") (name "unconnected-(U$1-3.3V1-PadP$20)") (class "Default")
      (node (ref "U$1") (pin "P$20") (pinfunction "3.3V1_P$20") (pintype "bidirectional"))
    )
    (net (code "72") (name "unconnected-(U$1-PA1-PadP$35)") (class "Default")
      (node (ref "U$1") (pin "P$35") (pinfunction "PA1_P$35") (pintype "bidirectional"))
    )
    (net (code "73") (name "unconnected-(U$1-PA2-PadP$34)") (class "Default")
      (node (ref "U$1") (pin "P$34") (pinfunction "PA2_P$34") (pintype "bidirectional"))
    )
    (net (code "74") (name "unconnected-(U$1-PA3-PadP$33)") (class "Default")
      (node (ref "U$1") (pin "P$33") (pinfunction "PA3_P$33") (pintype "bidirectional"))
    )
    (net (code "75") (name "unconnected-(U$1-PA11-PadP$8)") (class "Default")
      (node (ref "U$1") (pin "P$8") (pinfunction "PA11_P$8") (pintype "bidirectional"))
    )
    (net (code "76") (name "unconnected-(U$1-PA12-PadP$9)") (class "Default")
      (node (ref "U$1") (pin "P$9") (pinfunction "PA12_P$9") (pintype "bidirectional"))
    )
    (net (code "77") (name "unconnected-(U$1-PB1-PadP$27)") (class "Default")
      (node (ref "U$1") (pin "P$27") (pinfunction "PB1_P$27") (pintype "bidirectional"))
    )
    (net (code "78") (name "unconnected-(U$1-PC13-PadP$39)") (class "Default")
      (node (ref "U$1") (pin "P$39") (pinfunction "PC13_P$39") (pintype "bidirectional"))
    )
    (net (code "79") (name "unconnected-(U$1-VBAT-PadP$40)") (class "Default")
      (node (ref "U$1") (pin "P$40") (pinfunction "VBAT_P$40") (pintype "bidirectional"))
    )
    (net (code "80") (name "unconnected-(X1AB-S-Pad34)") (class "Default")
      (node (ref "X1") (pin "34") (pinfunction "S_34") (pintype "passive"))
    )
    (net (code "81") (name "unconnected-(X1R-S-Pad25)") (class "Default")
      (node (ref "X1") (pin "25") (pinfunction "S_25") (pintype "passive"))
    )
  )
)
